# INPUT.net
KiCad netlist of a schematic drawn in Altium Designer
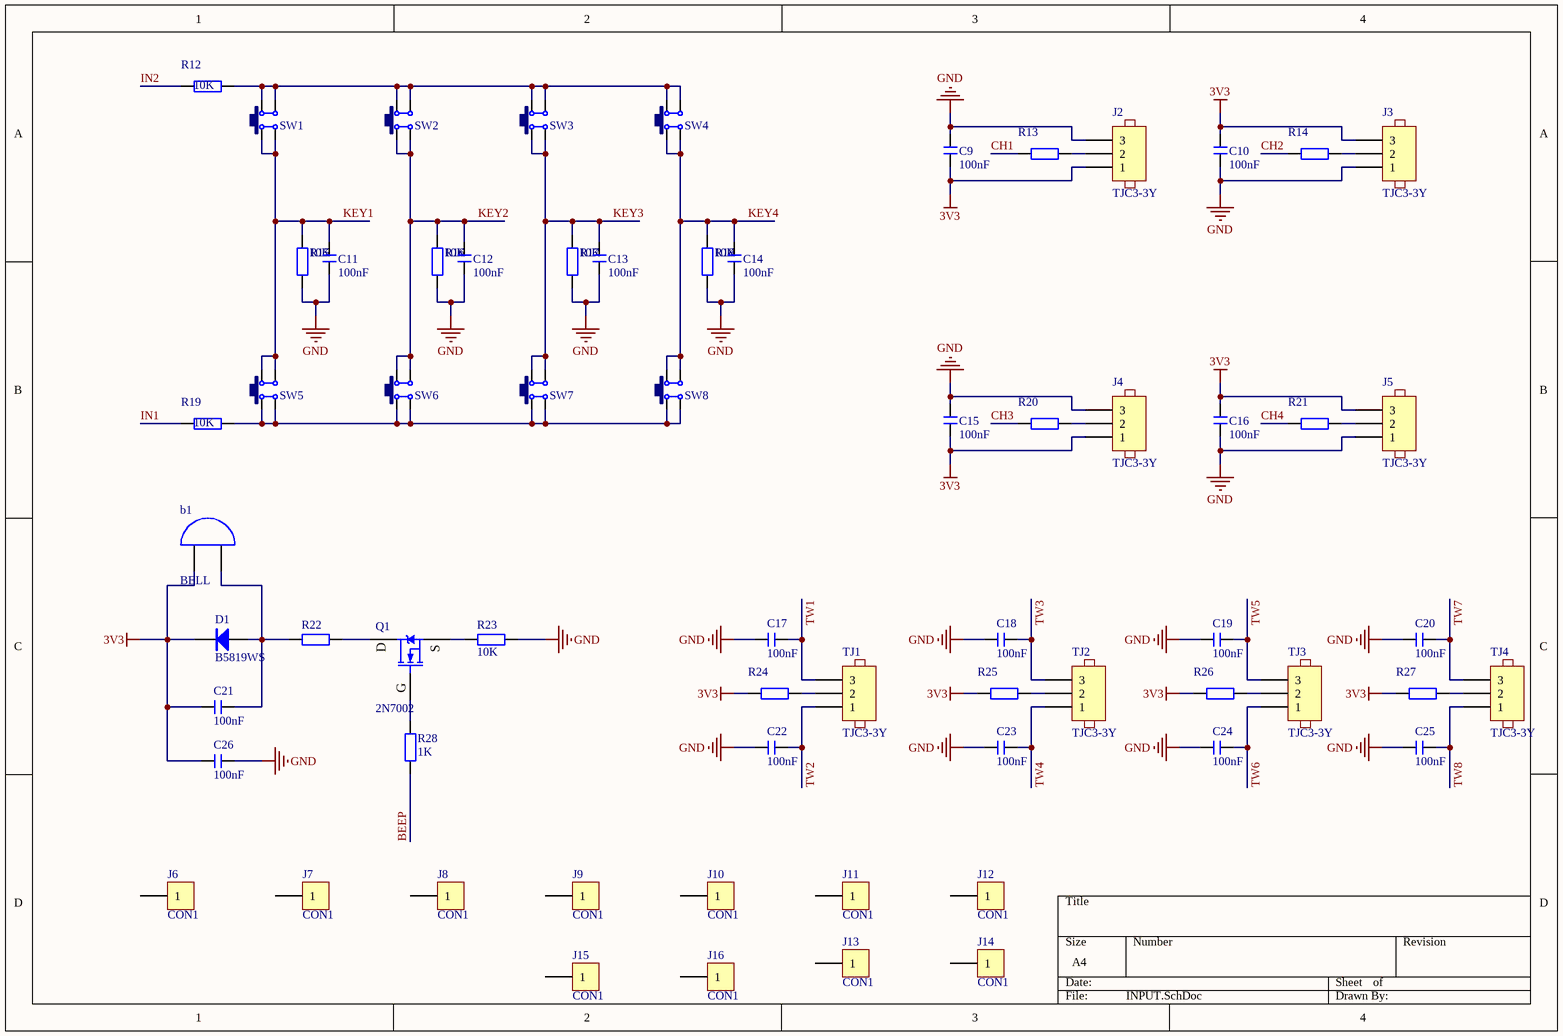
[diagram p0: INPUT.SchDoc]

(export (version "E")
  (design (tool "Eeschema 10.0.6"))
  (components
    (comp (ref "b1") (value "BELL") (footprint "BEEP 5x9x5.5") (libsource (lib "常用元件库") (part "BELL")))
    (comp (ref "C9")
      (value "100nF")
      (footprint "C 0603_L")
      (description "无极性贴片电容")
      (fields (field (name "版权归属") "源创客"))
      (libsource (lib "3.1   - 电阻-电容-电感") (part "C"))
    )
    (comp (ref "C10")
      (value "100nF")
      (footprint "C 0603_L")
      (description "无极性贴片电容")
      (fields (field (name "版权归属") "源创客"))
      (libsource (lib "3.1   - 电阻-电容-电感") (part "C"))
    )
    (comp (ref "C11")
      (value "100nF")
      (footprint "C 0603_L")
      (description "无极性贴片电容")
      (fields (field (name "版权归属") "源创客"))
      (libsource (lib "3.1   - 电阻-电容-电感") (part "C"))
    )
    (comp (ref "C12")
      (value "100nF")
      (footprint "C 0603_L")
      (description "无极性贴片电容")
      (fields (field (name "版权归属") "源创客"))
      (libsource (lib "3.1   - 电阻-电容-电感") (part "C"))
    )
    (comp (ref "C13")
      (value "100nF")
      (footprint "C 0603_L")
      (description "无极性贴片电容")
      (fields (field (name "版权归属") "源创客"))
      (libsource (lib "3.1   - 电阻-电容-电感") (part "C"))
    )
    (comp (ref "C14")
      (value "100nF")
      (footprint "C 0603_L")
      (description "无极性贴片电容")
      (fields (field (name "版权归属") "源创客"))
      (libsource (lib "3.1   - 电阻-电容-电感") (part "C"))
    )
    (comp (ref "C15")
      (value "100nF")
      (footprint "C 0603_L")
      (description "无极性贴片电容")
      (fields (field (name "版权归属") "源创客"))
      (libsource (lib "3.1   - 电阻-电容-电感") (part "C"))
    )
    (comp (ref "C16")
      (value "100nF")
      (footprint "C 0603_L")
      (description "无极性贴片电容")
      (fields (field (name "版权归属") "源创客"))
      (libsource (lib "3.1   - 电阻-电容-电感") (part "C"))
    )
    (comp (ref "C17")
      (value "100nF")
      (footprint "C 0603_L")
      (description "无极性贴片电容")
      (fields (field (name "版权归属") "源创客"))
      (libsource (lib "3.1   - 电阻-电容-电感") (part "C"))
    )
    (comp (ref "C18")
      (value "100nF")
      (footprint "C 0603_L")
      (description "无极性贴片电容")
      (fields (field (name "版权归属") "源创客"))
      (libsource (lib "3.1   - 电阻-电容-电感") (part "C"))
    )
    (comp (ref "C19")
      (value "100nF")
      (footprint "C 0603_L")
      (description "无极性贴片电容")
      (fields (field (name "版权归属") "源创客"))
      (libsource (lib "3.1   - 电阻-电容-电感") (part "C"))
    )
    (comp (ref "C20")
      (value "100nF")
      (footprint "C 0603_L")
      (description "无极性贴片电容")
      (fields (field (name "版权归属") "源创客"))
      (libsource (lib "3.1   - 电阻-电容-电感") (part "C"))
    )
    (comp (ref "C21")
      (value "100nF")
      (footprint "C 0603_L")
      (description "无极性贴片电容")
      (fields (field (name "版权归属") "源创客"))
      (libsource (lib "3.1   - 电阻-电容-电感") (part "C"))
    )
    (comp (ref "C22")
      (value "100nF")
      (footprint "C 0603_L")
      (description "无极性贴片电容")
      (fields (field (name "版权归属") "源创客"))
      (libsource (lib "3.1   - 电阻-电容-电感") (part "C"))
    )
    (comp (ref "C23")
      (value "100nF")
      (footprint "C 0603_L")
      (description "无极性贴片电容")
      (fields (field (name "版权归属") "源创客"))
      (libsource (lib "3.1   - 电阻-电容-电感") (part "C"))
    )
    (comp (ref "C24")
      (value "100nF")
      (footprint "C 0603_L")
      (description "无极性贴片电容")
      (fields (field (name "版权归属") "源创客"))
      (libsource (lib "3.1   - 电阻-电容-电感") (part "C"))
    )
    (comp (ref "C25")
      (value "100nF")
      (footprint "C 0603_L")
      (description "无极性贴片电容")
      (fields (field (name "版权归属") "源创客"))
      (libsource (lib "3.1   - 电阻-电容-电感") (part "C"))
    )
    (comp (ref "C26")
      (value "100nF")
      (footprint "C 0603_L")
      (description "无极性贴片电容")
      (fields (field (name "版权归属") "源创客"))
      (libsource (lib "3.1   - 电阻-电容-电感") (part "C"))
    )
    (comp (ref "D1")
      (value "B5819WS")
      (footprint "SOD-323")
      (description "肖特基二极管                           电压:40V 电流:1A                 C7420331")
      (fields (field (name "版权归属") "源创客"))
      (libsource (lib "8.1   - 二极管-整流桥") (part "SR540"))
    )
    (comp (ref "J2")
      (value "TJC3-3Y")
      (footprint "MX 1.25-LS-3P")
      (description "HCZZ0015-3             C7433469")
      (fields (field (name "PUBLISHER") "Altium Limited"))
      (libsource (lib "接口与插座") (part "TJC3-3Y"))
    )
    (comp (ref "J3")
      (value "TJC3-3Y")
      (footprint "MX 1.25-LS-3P")
      (description "HCZZ0015-3             C7433469")
      (fields (field (name "PUBLISHER") "Altium Limited"))
      (libsource (lib "接口与插座") (part "TJC3-3Y"))
    )
    (comp (ref "J4")
      (value "TJC3-3Y")
      (footprint "MX 1.25-LS-3P")
      (description "HCZZ0015-3             C7433469")
      (fields (field (name "PUBLISHER") "Altium Limited"))
      (libsource (lib "接口与插座") (part "TJC3-3Y"))
    )
    (comp (ref "J5")
      (value "TJC3-3Y")
      (footprint "MX 1.25-LS-3P")
      (description "HCZZ0015-3             C7433469")
      (fields (field (name "PUBLISHER") "Altium Limited"))
      (libsource (lib "接口与插座") (part "TJC3-3Y"))
    )
    (comp (ref "J6") (value "CON1") (footprint "M3x5+6_L") (libsource (lib "常用元件库") (part "CON1")))
    (comp (ref "J7") (value "CON1") (footprint "M3x5+6_L") (libsource (lib "常用元件库") (part "CON1")))
    (comp (ref "J8") (value "CON1") (footprint "M3x5+6_L") (libsource (lib "常用元件库") (part "CON1")))
    (comp (ref "J9") (value "CON1") (footprint "M3x5+6_L") (libsource (lib "常用元件库") (part "CON1")))
    (comp (ref "J10") (value "CON1") (footprint "M3x5+6_L") (libsource (lib "常用元件库") (part "CON1")))
    (comp (ref "J11") (value "CON1") (footprint "M3x5+6_L") (libsource (lib "常用元件库") (part "CON1")))
    (comp (ref "J12") (value "CON1") (footprint "M3x5+6_L") (libsource (lib "常用元件库") (part "CON1")))
    (comp (ref "J13") (value "CON1") (footprint "M3x5+6_L") (libsource (lib "常用元件库") (part "CON1")))
    (comp (ref "J14") (value "CON1") (footprint "M3x5+6_L") (libsource (lib "常用元件库") (part "CON1")))
    (comp (ref "J15") (value "CON1") (footprint "M3x5+6_L") (libsource (lib "常用元件库") (part "CON1")))
    (comp (ref "J16") (value "CON1") (footprint "M3x5+6_L") (libsource (lib "常用元件库") (part "CON1")))
    (comp (ref "Q1")
      (value "2N7002")
      (footprint "SOT-23")
      (description "N沟场效应管")
      (fields (field (name "版权归属") "源创客"))
      (libsource (lib "6.1   - 场效应管-可控硅") (part "IRF840"))
    )
    (comp (ref "R12")
      (value "10K")
      (footprint "R 0603_L")
      (description "贴片电阻")
      (fields (field (name "版权归属") "源创客"))
      (libsource (lib "3.1   - 电阻-电容-电感") (part "R"))
    )
    (comp (ref "R13")
      (value "~")
      (footprint "R 0603_L")
      (description "贴片电阻")
      (fields (field (name "版权归属") "源创客"))
      (libsource (lib "3.1   - 电阻-电容-电感") (part "R"))
    )
    (comp (ref "R14")
      (value "~")
      (footprint "R 0603_L")
      (description "贴片电阻")
      (fields (field (name "版权归属") "源创客"))
      (libsource (lib "3.1   - 电阻-电容-电感") (part "R"))
    )
    (comp (ref "R15")
      (value "10K")
      (footprint "R 0603_L")
      (description "贴片电阻")
      (fields (field (name "版权归属") "源创客"))
      (libsource (lib "3.1   - 电阻-电容-电感") (part "R"))
    )
    (comp (ref "R16")
      (value "10K")
      (footprint "R 0603_L")
      (description "贴片电阻")
      (fields (field (name "版权归属") "源创客"))
      (libsource (lib "3.1   - 电阻-电容-电感") (part "R"))
    )
    (comp (ref "R17")
      (value "10K")
      (footprint "R 0603_L")
      (description "贴片电阻")
      (fields (field (name "版权归属") "源创客"))
      (libsource (lib "3.1   - 电阻-电容-电感") (part "R"))
    )
    (comp (ref "R18")
      (value "10K")
      (footprint "R 0603_L")
      (description "贴片电阻")
      (fields (field (name "版权归属") "源创客"))
      (libsource (lib "3.1   - 电阻-电容-电感") (part "R"))
    )
    (comp (ref "R19")
      (value "10K")
      (footprint "R 0603_L")
      (description "贴片电阻")
      (fields (field (name "版权归属") "源创客"))
      (libsource (lib "3.1   - 电阻-电容-电感") (part "R"))
    )
    (comp (ref "R20")
      (value "~")
      (footprint "R 0603_L")
      (description "贴片电阻")
      (fields (field (name "版权归属") "源创客"))
      (libsource (lib "3.1   - 电阻-电容-电感") (part "R"))
    )
    (comp (ref "R21")
      (value "~")
      (footprint "R 0603_L")
      (description "贴片电阻")
      (fields (field (name "版权归属") "源创客"))
      (libsource (lib "3.1   - 电阻-电容-电感") (part "R"))
    )
    (comp (ref "R22")
      (value "~")
      (footprint "R 0603_L")
      (description "贴片电阻")
      (fields (field (name "版权归属") "源创客"))
      (libsource (lib "3.1   - 电阻-电容-电感") (part "R"))
    )
    (comp (ref "R23")
      (value "10K")
      (footprint "R 0603_L")
      (description "贴片电阻")
      (fields (field (name "版权归属") "源创客"))
      (libsource (lib "3.1   - 电阻-电容-电感") (part "R"))
    )
    (comp (ref "R24")
      (value "~")
      (footprint "R 0603_L")
      (description "贴片电阻")
      (fields (field (name "版权归属") "源创客"))
      (libsource (lib "3.1   - 电阻-电容-电感") (part "R"))
    )
    (comp (ref "R25")
      (value "~")
      (footprint "R 0603_L")
      (description "贴片电阻")
      (fields (field (name "版权归属") "源创客"))
      (libsource (lib "3.1   - 电阻-电容-电感") (part "R"))
    )
    (comp (ref "R26")
      (value "~")
      (footprint "R 0603_L")
      (description "贴片电阻")
      (fields (field (name "版权归属") "源创客"))
      (libsource (lib "3.1   - 电阻-电容-电感") (part "R"))
    )
    (comp (ref "R27")
      (value "~")
      (footprint "R 0603_L")
      (description "贴片电阻")
      (fields (field (name "版权归属") "源创客"))
      (libsource (lib "3.1   - 电阻-电容-电感") (part "R"))
    )
    (comp (ref "R28")
      (value "1K")
      (footprint "R 0603_L")
      (description "贴片电阻")
      (fields (field (name "版权归属") "源创客"))
      (libsource (lib "3.1   - 电阻-电容-电感") (part "R"))
    )
    (comp (ref "SW1")
      (value "6x6x5")
      (footprint "TSW SMD-6*6*5-L")
      (description "KH-6X6X5H-STM     C2837531")
      (fields (field (name "版权归属") "源创客"))
      (libsource (lib "5.1   - 按键-开关") (part "TSW SMD-6x6"))
    )
    (comp (ref "SW2")
      (value "6x6x5")
      (footprint "TSW SMD-6*6*5-L")
      (description "KH-6X6X5H-STM     C2837531")
      (fields (field (name "版权归属") "源创客"))
      (libsource (lib "5.1   - 按键-开关") (part "TSW SMD-6x6"))
    )
    (comp (ref "SW3")
      (value "6x6x5")
      (footprint "TSW SMD-6*6*5-L")
      (description "KH-6X6X5H-STM     C2837531")
      (fields (field (name "版权归属") "源创客"))
      (libsource (lib "5.1   - 按键-开关") (part "TSW SMD-6x6"))
    )
    (comp (ref "SW4")
      (value "6x6x5")
      (footprint "TSW SMD-6*6*5-L")
      (description "KH-6X6X5H-STM     C2837531")
      (fields (field (name "版权归属") "源创客"))
      (libsource (lib "5.1   - 按键-开关") (part "TSW SMD-6x6"))
    )
    (comp (ref "SW5")
      (value "6x6x5")
      (footprint "TSW SMD-6*6*5-L")
      (description "KH-6X6X5H-STM     C2837531")
      (fields (field (name "版权归属") "源创客"))
      (libsource (lib "5.1   - 按键-开关") (part "TSW SMD-6x6"))
    )
    (comp (ref "SW6")
      (value "6x6x5")
      (footprint "TSW SMD-6*6*5-L")
      (description "KH-6X6X5H-STM     C2837531")
      (fields (field (name "版权归属") "源创客"))
      (libsource (lib "5.1   - 按键-开关") (part "TSW SMD-6x6"))
    )
    (comp (ref "SW7")
      (value "6x6x5")
      (footprint "TSW SMD-6*6*5-L")
      (description "KH-6X6X5H-STM     C2837531")
      (fields (field (name "版权归属") "源创客"))
      (libsource (lib "5.1   - 按键-开关") (part "TSW SMD-6x6"))
    )
    (comp (ref "SW8")
      (value "6x6x5")
      (footprint "TSW SMD-6*6*5-L")
      (description "KH-6X6X5H-STM     C2837531")
      (fields (field (name "版权归属") "源创客"))
      (libsource (lib "5.1   - 按键-开关") (part "TSW SMD-6x6"))
    )
    (comp (ref "TJ1")
      (value "TJC3-3Y")
      (footprint "MX 1.25-LS-3P")
      (description "HCZZ0015-3             C7433469")
      (fields (field (name "PUBLISHER") "Altium Limited"))
      (libsource (lib "接口与插座") (part "TJC3-3Y"))
    )
    (comp (ref "TJ2")
      (value "TJC3-3Y")
      (footprint "MX 1.25-LS-3P")
      (description "HCZZ0015-3             C7433469")
      (fields (field (name "PUBLISHER") "Altium Limited"))
      (libsource (lib "接口与插座") (part "TJC3-3Y"))
    )
    (comp (ref "TJ3")
      (value "TJC3-3Y")
      (footprint "MX 1.25-LS-3P")
      (description "HCZZ0015-3             C7433469")
      (fields (field (name "PUBLISHER") "Altium Limited"))
      (libsource (lib "接口与插座") (part "TJC3-3Y"))
    )
    (comp (ref "TJ4")
      (value "TJC3-3Y")
      (footprint "MX 1.25-LS-3P")
      (description "HCZZ0015-3             C7433469")
      (fields (field (name "PUBLISHER") "Altium Limited"))
      (libsource (lib "接口与插座") (part "TJC3-3Y"))
    )
  )
  (nets
    (net (code "1") (name "/BEEP") (class "Default")
      (node (ref "R28") (pin "1") (pinfunction "1_1") (pintype "passive"))
    )
    (net (code "2") (name "/CH1") (class "Default")
      (node (ref "R13") (pin "2") (pinfunction "2_2") (pintype "passive"))
    )
    (net (code "3") (name "/CH2") (class "Default")
      (node (ref "R14") (pin "2") (pinfunction "2_2") (pintype "passive"))
    )
    (net (code "4") (name "/CH3") (class "Default")
      (node (ref "R20") (pin "2") (pinfunction "2_2") (pintype "passive"))
    )
    (net (code "5") (name "/CH4") (class "Default")
      (node (ref "R21") (pin "2") (pinfunction "2_2") (pintype "passive"))
    )
    (net (code "6") (name "/IN1") (class "Default")
      (node (ref "R19") (pin "2") (pinfunction "2_2") (pintype "passive"))
    )
    (net (code "7") (name "/IN2") (class "Default")
      (node (ref "R12") (pin "2") (pinfunction "2_2") (pintype "passive"))
    )
    (net (code "8") (name "/KEY1") (class "Default")
      (node (ref "C11") (pin "2") (pinfunction "2_2") (pintype "passive"))
      (node (ref "R15") (pin "1") (pinfunction "1_1") (pintype "passive"))
      (node (ref "SW1") (pin "1") (pinfunction "1_1") (pintype "passive"))
      (node (ref "SW1") (pin "4") (pinfunction "4_4") (pintype "passive"))
      (node (ref "SW5") (pin "2") (pinfunction "2_2") (pintype "passive"))
      (node (ref "SW5") (pin "3") (pinfunction "3_3") (pintype "passive"))
    )
    (net (code "9") (name "/KEY2") (class "Default")
      (node (ref "C12") (pin "2") (pinfunction "2_2") (pintype "passive"))
      (node (ref "R16") (pin "1") (pinfunction "1_1") (pintype "passive"))
      (node (ref "SW2") (pin "1") (pinfunction "1_1") (pintype "passive"))
      (node (ref "SW2") (pin "4") (pinfunction "4_4") (pintype "passive"))
      (node (ref "SW6") (pin "2") (pinfunction "2_2") (pintype "passive"))
      (node (ref "SW6") (pin "3") (pinfunction "3_3") (pintype "passive"))
    )
    (net (code "10") (name "/KEY3") (class "Default")
      (node (ref "C13") (pin "2") (pinfunction "2_2") (pintype "passive"))
      (node (ref "R17") (pin "1") (pinfunction "1_1") (pintype "passive"))
      (node (ref "SW3") (pin "1") (pinfunction "1_1") (pintype "passive"))
      (node (ref "SW3") (pin "4") (pinfunction "4_4") (pintype "passive"))
      (node (ref "SW7") (pin "2") (pinfunction "2_2") (pintype "passive"))
      (node (ref "SW7") (pin "3") (pinfunction "3_3") (pintype "passive"))
    )
    (net (code "11") (name "/KEY4") (class "Default")
      (node (ref "C14") (pin "2") (pinfunction "2_2") (pintype "passive"))
      (node (ref "R18") (pin "1") (pinfunction "1_1") (pintype "passive"))
      (node (ref "SW4") (pin "1") (pinfunction "1_1") (pintype "passive"))
      (node (ref "SW4") (pin "4") (pinfunction "4_4") (pintype "passive"))
      (node (ref "SW8") (pin "2") (pinfunction "2_2") (pintype "passive"))
      (node (ref "SW8") (pin "3") (pinfunction "3_3") (pintype "passive"))
    )
    (net (code "12") (name "/TW1") (class "Default")
      (node (ref "C17") (pin "1") (pinfunction "1_1") (pintype "passive"))
      (node (ref "TJ1") (pin "3") (pinfunction "3_3") (pintype "passive"))
    )
    (net (code "13") (name "/TW2") (class "Default")
      (node (ref "C22") (pin "1") (pinfunction "1_1") (pintype "passive"))
      (node (ref "TJ1") (pin "1") (pinfunction "1_1") (pintype "passive"))
    )
    (net (code "14") (name "/TW3") (class "Default")
      (node (ref "C18") (pin "1") (pinfunction "1_1") (pintype "passive"))
      (node (ref "TJ2") (pin "3") (pinfunction "3_3") (pintype "passive"))
    )
    (net (code "15") (name "/TW4") (class "Default")
      (node (ref "C23") (pin "1") (pinfunction "1_1") (pintype "passive"))
      (node (ref "TJ2") (pin "1") (pinfunction "1_1") (pintype "passive"))
    )
    (net (code "16") (name "/TW5") (class "Default")
      (node (ref "C19") (pin "1") (pinfunction "1_1") (pintype "passive"))
      (node (ref "TJ3") (pin "3") (pinfunction "3_3") (pintype "passive"))
    )
    (net (code "17") (name "/TW6") (class "Default")
      (node (ref "C24") (pin "1") (pinfunction "1_1") (pintype "passive"))
      (node (ref "TJ3") (pin "1") (pinfunction "1_1") (pintype "passive"))
    )
    (net (code "18") (name "/TW7") (class "Default")
      (node (ref "C20") (pin "1") (pinfunction "1_1") (pintype "passive"))
      (node (ref "TJ4") (pin "3") (pinfunction "3_3") (pintype "passive"))
    )
    (net (code "19") (name "/TW8") (class "Default")
      (node (ref "C25") (pin "1") (pinfunction "1_1") (pintype "passive"))
      (node (ref "TJ4") (pin "1") (pinfunction "1_1") (pintype "passive"))
    )
    (net (code "20") (name "3V3") (class "Default")
      (node (ref "C10") (pin "2") (pinfunction "2_2") (pintype "passive"))
      (node (ref "C15") (pin "1") (pinfunction "1_1") (pintype "passive"))
      (node (ref "C16") (pin "2") (pinfunction "2_2") (pintype "passive"))
      (node (ref "C21") (pin "2") (pinfunction "2_2") (pintype "passive"))
      (node (ref "C26") (pin "2") (pinfunction "2_2") (pintype "passive"))
      (node (ref "C9") (pin "1") (pinfunction "1_1") (pintype "passive"))
      (node (ref "D1") (pin "2") (pinfunction "K_2") (pintype "passive"))
      (node (ref "J2") (pin "1") (pinfunction "1_1") (pintype "passive"))
      (node (ref "J3") (pin "3") (pinfunction "3_3") (pintype "passive"))
      (node (ref "J4") (pin "1") (pinfunction "1_1") (pintype "passive"))
      (node (ref "J5") (pin "3") (pinfunction "3_3") (pintype "passive"))
      (node (ref "R24") (pin "2") (pinfunction "2_2") (pintype "passive"))
      (node (ref "R25") (pin "2") (pinfunction "2_2") (pintype "passive"))
      (node (ref "R26") (pin "2") (pinfunction "2_2") (pintype "passive"))
      (node (ref "R27") (pin "2") (pinfunction "2_2") (pintype "passive"))
      (node (ref "b1") (pin "1") (pinfunction "1_1") (pintype "passive"))
    )
    (net (code "21") (name "GND") (class "Default")
      (node (ref "C10") (pin "1") (pinfunction "1_1") (pintype "passive"))
      (node (ref "C11") (pin "1") (pinfunction "1_1") (pintype "passive"))
      (node (ref "C12") (pin "1") (pinfunction "1_1") (pintype "passive"))
      (node (ref "C13") (pin "1") (pinfunction "1_1") (pintype "passive"))
      (node (ref "C14") (pin "1") (pinfunction "1_1") (pintype "passive"))
      (node (ref "C15") (pin "2") (pinfunction "2_2") (pintype "passive"))
      (node (ref "C16") (pin "1") (pinfunction "1_1") (pintype "passive"))
      (node (ref "C17") (pin "2") (pinfunction "2_2") (pintype "passive"))
      (node (ref "C18") (pin "2") (pinfunction "2_2") (pintype "passive"))
      (node (ref "C19") (pin "2") (pinfunction "2_2") (pintype "passive"))
      (node (ref "C20") (pin "2") (pinfunction "2_2") (pintype "passive"))
      (node (ref "C22") (pin "2") (pinfunction "2_2") (pintype "passive"))
      (node (ref "C23") (pin "2") (pinfunction "2_2") (pintype "passive"))
      (node (ref "C24") (pin "2") (pinfunction "2_2") (pintype "passive"))
      (node (ref "C25") (pin "2") (pinfunction "2_2") (pintype "passive"))
      (node (ref "C26") (pin "1") (pinfunction "1_1") (pintype "passive"))
      (node (ref "C9") (pin "2") (pinfunction "2_2") (pintype "passive"))
      (node (ref "J2") (pin "3") (pinfunction "3_3") (pintype "passive"))
      (node (ref "J3") (pin "1") (pinfunction "1_1") (pintype "passive"))
      (node (ref "J4") (pin "3") (pinfunction "3_3") (pintype "passive"))
      (node (ref "J5") (pin "1") (pinfunction "1_1") (pintype "passive"))
      (node (ref "R15") (pin "2") (pinfunction "2_2") (pintype "passive"))
      (node (ref "R16") (pin "2") (pinfunction "2_2") (pintype "passive"))
      (node (ref "R17") (pin "2") (pinfunction "2_2") (pintype "passive"))
      (node (ref "R18") (pin "2") (pinfunction "2_2") (pintype "passive"))
      (node (ref "R23") (pin "1") (pinfunction "1_1") (pintype "passive"))
    )
    (net (code "22") (name "Net-(D1-A)") (class "Default")
      (node (ref "C21") (pin "1") (pinfunction "1_1") (pintype "passive"))
      (node (ref "D1") (pin "1") (pinfunction "A_1") (pintype "passive"))
      (node (ref "R22") (pin "1") (pinfunction "1_1") (pintype "passive"))
      (node (ref "b1") (pin "2") (pinfunction "2_2") (pintype "passive"))
    )
    (net (code "23") (name "Net-(J2-Pad2)") (class "Default")
      (node (ref "J2") (pin "2") (pinfunction "2_2") (pintype "passive"))
      (node (ref "R13") (pin "1") (pinfunction "1_1") (pintype "passive"))
    )
    (net (code "24") (name "Net-(J3-Pad2)") (class "Default")
      (node (ref "J3") (pin "2") (pinfunction "2_2") (pintype "passive"))
      (node (ref "R14") (pin "1") (pinfunction "1_1") (pintype "passive"))
    )
    (net (code "25") (name "Net-(J4-Pad2)") (class "Default")
      (node (ref "J4") (pin "2") (pinfunction "2_2") (pintype "passive"))
      (node (ref "R20") (pin "1") (pinfunction "1_1") (pintype "passive"))
    )
    (net (code "26") (name "Net-(J5-Pad2)") (class "Default")
      (node (ref "J5") (pin "2") (pinfunction "2_2") (pintype "passive"))
      (node (ref "R21") (pin "1") (pinfunction "1_1") (pintype "passive"))
    )
    (net (code "27") (name "Net-(Q1-D)") (class "Default")
      (node (ref "Q1") (pin "2") (pinfunction "D_2") (pintype "passive"))
      (node (ref "R22") (pin "2") (pinfunction "2_2") (pintype "passive"))
    )
    (net (code "28") (name "Net-(Q1-G)") (class "Default")
      (node (ref "Q1") (pin "1") (pinfunction "G_1") (pintype "passive"))
      (node (ref "R28") (pin "2") (pinfunction "2_2") (pintype "passive"))
    )
    (net (code "29") (name "Net-(Q1-S)") (class "Default")
      (node (ref "Q1") (pin "3") (pinfunction "S_3") (pintype "passive"))
      (node (ref "R23") (pin "2") (pinfunction "2_2") (pintype "passive"))
    )
    (net (code "30") (name "Net-(R12-Pad1)") (class "Default")
      (node (ref "R12") (pin "1") (pinfunction "1_1") (pintype "passive"))
      (node (ref "SW1") (pin "2") (pinfunction "2_2") (pintype "passive"))
      (node (ref "SW1") (pin "3") (pinfunction "3_3") (pintype "passive"))
      (node (ref "SW2") (pin "2") (pinfunction "2_2") (pintype "passive"))
      (node (ref "SW2") (pin "3") (pinfunction "3_3") (pintype "passive"))
      (node (ref "SW3") (pin "2") (pinfunction "2_2") (pintype "passive"))
      (node (ref "SW3") (pin "3") (pinfunction "3_3") (pintype "passive"))
      (node (ref "SW4") (pin "2") (pinfunction "2_2") (pintype "passive"))
      (node (ref "SW4") (pin "3") (pinfunction "3_3") (pintype "passive"))
    )
    (net (code "31") (name "Net-(R19-Pad1)") (class "Default")
      (node (ref "R19") (pin "1") (pinfunction "1_1") (pintype "passive"))
      (node (ref "SW5") (pin "1") (pinfunction "1_1") (pintype "passive"))
      (node (ref "SW5") (pin "4") (pinfunction "4_4") (pintype "passive"))
      (node (ref "SW6") (pin "1") (pinfunction "1_1") (pintype "passive"))
      (node (ref "SW6") (pin "4") (pinfunction "4_4") (pintype "passive"))
      (node (ref "SW7") (pin "1") (pinfunction "1_1") (pintype "passive"))
      (node (ref "SW7") (pin "4") (pinfunction "4_4") (pintype "passive"))
      (node (ref "SW8") (pin "1") (pinfunction "1_1") (pintype "passive"))
      (node (ref "SW8") (pin "4") (pinfunction "4_4") (pintype "passive"))
    )
    (net (code "32") (name "Net-(R24-Pad1)") (class "Default")
      (node (ref "R24") (pin "1") (pinfunction "1_1") (pintype "passive"))
      (node (ref "TJ1") (pin "2") (pinfunction "2_2") (pintype "passive"))
    )
    (net (code "33") (name "Net-(R25-Pad1)") (class "Default")
      (node (ref "R25") (pin "1") (pinfunction "1_1") (pintype "passive"))
      (node (ref "TJ2") (pin "2") (pinfunction "2_2") (pintype "passive"))
    )
    (net (code "34") (name "Net-(R26-Pad1)") (class "Default")
      (node (ref "R26") (pin "1") (pinfunction "1_1") (pintype "passive"))
      (node (ref "TJ3") (pin "2") (pinfunction "2_2") (pintype "passive"))
    )
    (net (code "35") (name "Net-(R27-Pad1)") (class "Default")
      (node (ref "R27") (pin "1") (pinfunction "1_1") (pintype "passive"))
      (node (ref "TJ4") (pin "2") (pinfunction "2_2") (pintype "passive"))
    )
    (net (code "36") (name "unconnected-(J6-Pad1)") (class "Default")
      (node (ref "J6") (pin "1") (pinfunction "1_1") (pintype "passive"))
    )
    (net (code "37") (name "unconnected-(J7-Pad1)") (class "Default")
      (node (ref "J7") (pin "1") (pinfunction "1_1") (pintype "passive"))
    )
    (net (code "38") (name "unconnected-(J8-Pad1)") (class "Default")
      (node (ref "J8") (pin "1") (pinfunction "1_1") (pintype "passive"))
    )
    (net (code "39") (name "unconnected-(J9-Pad1)") (class "Default")
      (node (ref "J9") (pin "1") (pinfunction "1_1") (pintype "passive"))
    )
    (net (code "40") (name "unconnected-(J10-Pad1)") (class "Default")
      (node (ref "J10") (pin "1") (pinfunction "1_1") (pintype "passive"))
    )
    (net (code "41") (name "unconnected-(J11-Pad1)") (class "Default")
      (node (ref "J11") (pin "1") (pinfunction "1_1") (pintype "passive"))
    )
    (net (code "42") (name "unconnected-(J12-Pad1)") (class "Default")
      (node (ref "J12") (pin "1") (pinfunction "1_1") (pintype "passive"))
    )
    (net (code "43") (name "unconnected-(J13-Pad1)") (class "Default")
      (node (ref "J13") (pin "1") (pinfunction "1_1") (pintype "passive"))
    )
    (net (code "44") (name "unconnected-(J14-Pad1)") (class "Default")
      (node (ref "J14") (pin "1") (pinfunction "1_1") (pintype "passive"))
    )
    (net (code "45") (name "unconnected-(J15-Pad1)") (class "Default")
      (node (ref "J15") (pin "1") (pinfunction "1_1") (pintype "passive"))
    )
    (net (code "46") (name "unconnected-(J16-Pad1)") (class "Default")
      (node (ref "J16") (pin "1") (pinfunction "1_1") (pintype "passive"))
    )
  )
)
